# RP2040.net
KiCad netlist of a schematic drawn in Altium Designer
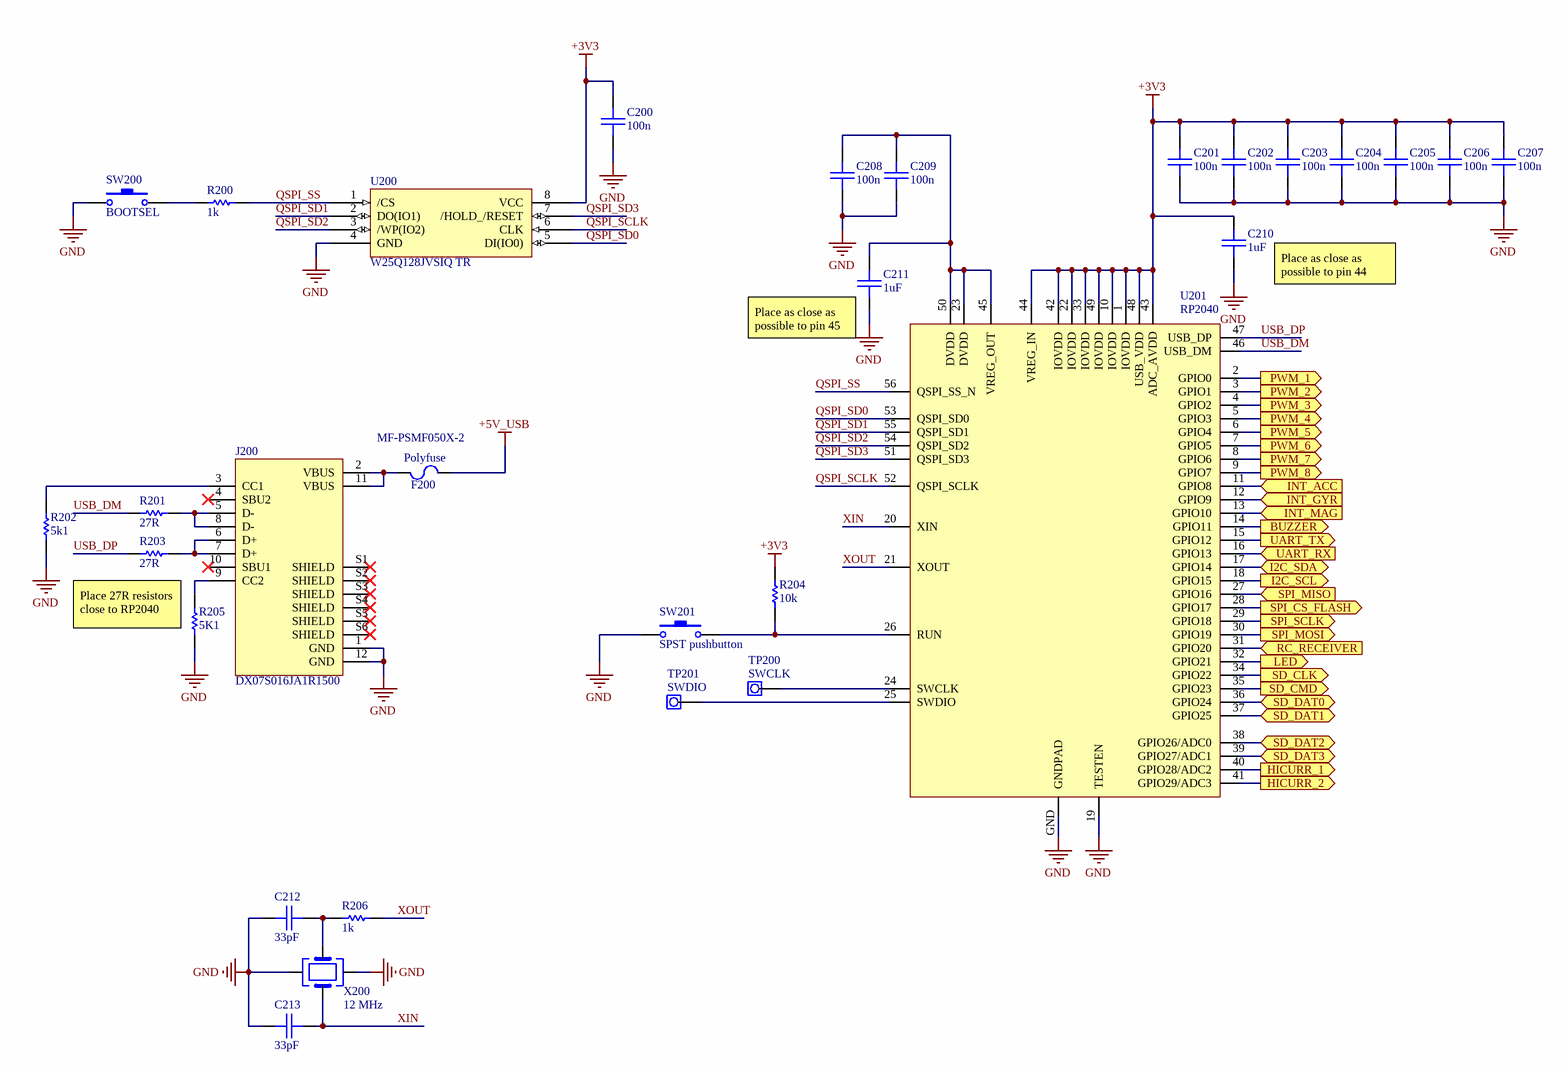
[diagram p0: RP2040.SchDoc]

(export (version "E")
  (design (tool "Eeschema 10.0.6"))
  (components
    (comp (ref "C200")
      (value "100n")
      (footprint "0603_CAP")
      (libsource (lib "Moonlight_Components") (part "Capacitor"))
    )
    (comp (ref "C201")
      (value "100n")
      (footprint "0603_CAP")
      (libsource (lib "Moonlight_Components") (part "Capacitor"))
    )
    (comp (ref "C202")
      (value "100n")
      (footprint "0603_CAP")
      (libsource (lib "Moonlight_Components") (part "Capacitor"))
    )
    (comp (ref "C203")
      (value "100n")
      (footprint "0603_CAP")
      (libsource (lib "Moonlight_Components") (part "Capacitor"))
    )
    (comp (ref "C204")
      (value "100n")
      (footprint "0603_CAP")
      (libsource (lib "Moonlight_Components") (part "Capacitor"))
    )
    (comp (ref "C205")
      (value "100n")
      (footprint "0603_CAP")
      (libsource (lib "Moonlight_Components") (part "Capacitor"))
    )
    (comp (ref "C206")
      (value "100n")
      (footprint "0603_CAP")
      (libsource (lib "Moonlight_Components") (part "Capacitor"))
    )
    (comp (ref "C207")
      (value "100n")
      (footprint "0603_CAP")
      (libsource (lib "Moonlight_Components") (part "Capacitor"))
    )
    (comp (ref "C208")
      (value "100n")
      (footprint "0603_CAP")
      (libsource (lib "Moonlight_Components") (part "Capacitor"))
    )
    (comp (ref "C209")
      (value "100n")
      (footprint "0603_CAP")
      (libsource (lib "Moonlight_Components") (part "Capacitor"))
    )
    (comp (ref "C210")
      (value "1uF")
      (footprint "0603_CAP")
      (libsource (lib "Moonlight_Components") (part "Capacitor"))
    )
    (comp (ref "C211")
      (value "1uF")
      (footprint "0603_CAP")
      (libsource (lib "Moonlight_Components") (part "Capacitor"))
    )
    (comp (ref "C212")
      (value "33pF")
      (footprint "0603_CAP")
      (libsource (lib "Moonlight_Components") (part "Capacitor"))
    )
    (comp (ref "C213")
      (value "33pF")
      (footprint "0603_CAP")
      (libsource (lib "Moonlight_Components") (part "Capacitor"))
    )
    (comp (ref "F200")
      (value "Polyfuse")
      (footprint "0805")
      (libsource (lib "Moonlight_Components") (part "Fuse"))
    )
    (comp (ref "J200")
      (value "DX07S016JA1R1500")
      (footprint "JAE_DX07S016JA1R1500")
      (description "USB 2.0 Type C Receptacle Dip Type, PCB Top Mount (Digikey part no. 670-DX07S016JA1R1500CT-ND)")
      (fields (field (name "MF") "JAE Electronics"))
      (libsource (lib "Moonlight_Components") (part "DX07S016JA1R1500"))
    )
    (comp (ref "R200")
      (value "1k")
      (footprint "0603_RES")
      (libsource (lib "Moonlight_Components") (part "Resistor"))
    )
    (comp (ref "R201")
      (value "27R")
      (footprint "0603_RES")
      (libsource (lib "Moonlight_Components") (part "Resistor"))
    )
    (comp (ref "R202")
      (value "5k1")
      (footprint "0603_RES")
      (libsource (lib "Moonlight_Components") (part "Resistor"))
    )
    (comp (ref "R203")
      (value "27R")
      (footprint "0603_RES")
      (libsource (lib "Moonlight_Components") (part "Resistor"))
    )
    (comp (ref "R204")
      (value "10k")
      (footprint "0805_RES")
      (libsource (lib "Moonlight_Components") (part "Resistor"))
    )
    (comp (ref "R205")
      (value "5K1")
      (footprint "0603_RES")
      (libsource (lib "Moonlight_Components") (part "Resistor"))
    )
    (comp (ref "R206")
      (value "1k")
      (footprint "0603_RES")
      (libsource (lib "Moonlight_Components") (part "Resistor"))
    )
    (comp (ref "SW200")
      (value "BOOTSEL")
      (footprint "TL1015")
      (description "DigiKey part no. EG4344CT-ND")
      (libsource (lib "Moonlight_Components") (part "PushButton"))
    )
    (comp (ref "SW201")
      (value "SPST pushbutton")
      (footprint "TL1015")
      (description "DigiKey part no. EG4344CT-ND")
      (libsource (lib "Moonlight_Components") (part "PushButton"))
    )
    (comp (ref "TP200")
      (value "SWCLK")
      (footprint "Testpoint")
      (libsource (lib "Moonlight_Components") (part "Testpoint"))
    )
    (comp (ref "TP201")
      (value "SWDIO")
      (footprint "Testpoint")
      (libsource (lib "Moonlight_Components") (part "Testpoint"))
    )
    (comp (ref "U200")
      (value "W25Q128JVSIQ TR")
      (footprint "SOIC_208MIL_WIN")
      (description "No Description Available")
      (fields (field (name "COPYRIGHT") "Copyright (C) 2018 Accelerated Designs. All rights reserved"))
      (libsource (lib "Moonlight_Components") (part "W25Q128JVSIQ TR"))
    )
    (comp (ref "U201")
      (value "RP2040")
      (footprint "RP2040")
      (libsource (lib "Moonlight_Components") (part "RP2040"))
    )
    (comp (ref "X200")
      (value "12 MHz")
      (footprint "XOSC_3.2mmx2.5mm")
      (description "12 MHz crystal oscillator\r\nECS-120-20-33-CKM-TR\r\nDigiKey part no. XC1810CT-ND")
      (libsource (lib "Moonlight_Components") (part "XTAL_12 MHz"))
    )
  )
  (nets
    (net (code "1") (name "+3V3") (class "Default")
      (node (ref "C200") (pin "1") (pinfunction "1_1") (pintype "passive"))
      (node (ref "C201") (pin "1") (pinfunction "1_1") (pintype "passive"))
      (node (ref "C202") (pin "1") (pinfunction "1_1") (pintype "passive"))
      (node (ref "C203") (pin "1") (pinfunction "1_1") (pintype "passive"))
      (node (ref "C204") (pin "1") (pinfunction "1_1") (pintype "passive"))
      (node (ref "C205") (pin "1") (pinfunction "1_1") (pintype "passive"))
      (node (ref "C206") (pin "1") (pinfunction "1_1") (pintype "passive"))
      (node (ref "C207") (pin "1") (pinfunction "1_1") (pintype "passive"))
      (node (ref "C210") (pin "1") (pinfunction "1_1") (pintype "passive"))
      (node (ref "R204") (pin "1") (pinfunction "1_1") (pintype "passive"))
      (node (ref "U200") (pin "8") (pinfunction "VCC_8") (pintype "power_in"))
      (node (ref "U201") (pin "1") (pinfunction "IOVDD_1") (pintype "passive"))
      (node (ref "U201") (pin "10") (pinfunction "IOVDD_10") (pintype "passive"))
      (node (ref "U201") (pin "22") (pinfunction "IOVDD_22") (pintype "passive"))
      (node (ref "U201") (pin "33") (pinfunction "IOVDD_33") (pintype "passive"))
      (node (ref "U201") (pin "42") (pinfunction "IOVDD_42") (pintype "passive"))
      (node (ref "U201") (pin "43") (pinfunction "ADC_AVDD_43") (pintype "passive"))
      (node (ref "U201") (pin "44") (pinfunction "VREG_IN_44") (pintype "passive"))
      (node (ref "U201") (pin "48") (pinfunction "USB_VDD_48") (pintype "passive"))
      (node (ref "U201") (pin "49") (pinfunction "IOVDD_49") (pintype "passive"))
    )
    (net (code "2") (name "+5V_USB") (class "Default")
      (node (ref "F200") (pin "2") (pinfunction "2_2") (pintype "passive"))
    )
    (net (code "3") (name "/BUZZER") (class "Default")
      (node (ref "U201") (pin "14") (pinfunction "GPIO11_14") (pintype "passive"))
    )
    (net (code "4") (name "/HICURR_1") (class "Default")
      (node (ref "U201") (pin "40") (pinfunction "GPIO28/ADC2_40") (pintype "passive"))
    )
    (net (code "5") (name "/HICURR_2") (class "Default")
      (node (ref "U201") (pin "41") (pinfunction "GPIO29/ADC3_41") (pintype "passive"))
    )
    (net (code "6") (name "/I2C_SCL") (class "Default")
      (node (ref "U201") (pin "18") (pinfunction "GPIO15_18") (pintype "passive"))
    )
    (net (code "7") (name "/I2C_SDA") (class "Default")
      (node (ref "U201") (pin "17") (pinfunction "GPIO14_17") (pintype "passive"))
    )
    (net (code "8") (name "/INT_ACC") (class "Default")
      (node (ref "U201") (pin "11") (pinfunction "GPIO8_11") (pintype "passive"))
    )
    (net (code "9") (name "/INT_GYR") (class "Default")
      (node (ref "U201") (pin "12") (pinfunction "GPIO9_12") (pintype "passive"))
    )
    (net (code "10") (name "/INT_MAG") (class "Default")
      (node (ref "U201") (pin "13") (pinfunction "GPIO10_13") (pintype "passive"))
    )
    (net (code "11") (name "/LED") (class "Default")
      (node (ref "U201") (pin "32") (pinfunction "GPIO21_32") (pintype "passive"))
    )
    (net (code "12") (name "/PWM_1") (class "Default")
      (node (ref "U201") (pin "2") (pinfunction "GPIO0_2") (pintype "passive"))
    )
    (net (code "13") (name "/PWM_2") (class "Default")
      (node (ref "U201") (pin "3") (pinfunction "GPIO1_3") (pintype "passive"))
    )
    (net (code "14") (name "/PWM_3") (class "Default")
      (node (ref "U201") (pin "4") (pinfunction "GPIO2_4") (pintype "passive"))
    )
    (net (code "15") (name "/PWM_4") (class "Default")
      (node (ref "U201") (pin "5") (pinfunction "GPIO3_5") (pintype "passive"))
    )
    (net (code "16") (name "/PWM_5") (class "Default")
      (node (ref "U201") (pin "6") (pinfunction "GPIO4_6") (pintype "passive"))
    )
    (net (code "17") (name "/PWM_6") (class "Default")
      (node (ref "U201") (pin "7") (pinfunction "GPIO5_7") (pintype "passive"))
    )
    (net (code "18") (name "/PWM_7") (class "Default")
      (node (ref "U201") (pin "8") (pinfunction "GPIO6_8") (pintype "passive"))
    )
    (net (code "19") (name "/PWM_8") (class "Default")
      (node (ref "U201") (pin "9") (pinfunction "GPIO7_9") (pintype "passive"))
    )
    (net (code "20") (name "/QSPI_SCLK") (class "Default")
      (node (ref "U200") (pin "6") (pinfunction "CLK_6") (pintype "input"))
      (node (ref "U201") (pin "52") (pinfunction "QSPI_SCLK_52") (pintype "passive"))
    )
    (net (code "21") (name "/QSPI_SD0") (class "Default")
      (node (ref "U200") (pin "5") (pinfunction "DI(IO0)_5") (pintype "bidirectional"))
      (node (ref "U201") (pin "53") (pinfunction "QSPI_SD0_53") (pintype "passive"))
    )
    (net (code "22") (name "/QSPI_SD1") (class "Default")
      (node (ref "U200") (pin "2") (pinfunction "DO(IO1)_2") (pintype "bidirectional"))
      (node (ref "U201") (pin "55") (pinfunction "QSPI_SD1_55") (pintype "passive"))
    )
    (net (code "23") (name "/QSPI_SD2") (class "Default")
      (node (ref "U200") (pin "3") (pinfunction "/WP(IO2)_3") (pintype "bidirectional"))
      (node (ref "U201") (pin "54") (pinfunction "QSPI_SD2_54") (pintype "passive"))
    )
    (net (code "24") (name "/QSPI_SD3") (class "Default")
      (node (ref "U200") (pin "7") (pinfunction "/HOLD_/RESET_7") (pintype "bidirectional"))
      (node (ref "U201") (pin "51") (pinfunction "QSPI_SD3_51") (pintype "passive"))
    )
    (net (code "25") (name "/QSPI_SS") (class "Default")
      (node (ref "R200") (pin "2") (pinfunction "2_2") (pintype "passive"))
      (node (ref "U200") (pin "1") (pinfunction "/CS_1") (pintype "input"))
      (node (ref "U201") (pin "56") (pinfunction "QSPI_SS_N_56") (pintype "passive"))
    )
    (net (code "26") (name "/RC_RECEIVER") (class "Default")
      (node (ref "U201") (pin "31") (pinfunction "GPIO20_31") (pintype "passive"))
    )
    (net (code "27") (name "/SD_CLK") (class "Default")
      (node (ref "U201") (pin "34") (pinfunction "GPIO22_34") (pintype "passive"))
    )
    (net (code "28") (name "/SD_CMD") (class "Default")
      (node (ref "U201") (pin "35") (pinfunction "GPIO23_35") (pintype "passive"))
    )
    (net (code "29") (name "/SD_DAT0") (class "Default")
      (node (ref "U201") (pin "36") (pinfunction "GPIO24_36") (pintype "passive"))
    )
    (net (code "30") (name "/SD_DAT1") (class "Default")
      (node (ref "U201") (pin "37") (pinfunction "GPIO25_37") (pintype "passive"))
    )
    (net (code "31") (name "/SD_DAT2") (class "Default")
      (node (ref "U201") (pin "38") (pinfunction "GPIO26/ADC0_38") (pintype "passive"))
    )
    (net (code "32") (name "/SD_DAT3") (class "Default")
      (node (ref "U201") (pin "39") (pinfunction "GPIO27/ADC1_39") (pintype "passive"))
    )
    (net (code "33") (name "/SPI_CS_FLASH") (class "Default")
      (node (ref "U201") (pin "28") (pinfunction "GPIO17_28") (pintype "passive"))
    )
    (net (code "34") (name "/SPI_MISO") (class "Default")
      (node (ref "U201") (pin "27") (pinfunction "GPIO16_27") (pintype "passive"))
    )
    (net (code "35") (name "/SPI_MOSI") (class "Default")
      (node (ref "U201") (pin "30") (pinfunction "GPIO19_30") (pintype "passive"))
    )
    (net (code "36") (name "/SPI_SCLK") (class "Default")
      (node (ref "U201") (pin "29") (pinfunction "GPIO18_29") (pintype "passive"))
    )
    (net (code "37") (name "/UART_RX") (class "Default")
      (node (ref "U201") (pin "16") (pinfunction "GPIO13_16") (pintype "passive"))
    )
    (net (code "38") (name "/UART_TX") (class "Default")
      (node (ref "U201") (pin "15") (pinfunction "GPIO12_15") (pintype "passive"))
    )
    (net (code "39") (name "/USB_DM") (class "Default")
      (node (ref "R201") (pin "1") (pinfunction "1_1") (pintype "passive"))
      (node (ref "U201") (pin "46") (pinfunction "USB_DM_46") (pintype "passive"))
    )
    (net (code "40") (name "/USB_DP") (class "Default")
      (node (ref "R203") (pin "1") (pinfunction "1_1") (pintype "passive"))
      (node (ref "U201") (pin "47") (pinfunction "USB_DP_47") (pintype "passive"))
    )
    (net (code "41") (name "/XIN") (class "Default")
      (node (ref "C213") (pin "1") (pinfunction "1_1") (pintype "passive"))
      (node (ref "U201") (pin "20") (pinfunction "XIN_20") (pintype "passive"))
      (node (ref "X200") (pin "1") (pinfunction "1_1") (pintype "passive"))
    )
    (net (code "42") (name "/XOUT") (class "Default")
      (node (ref "R206") (pin "1") (pinfunction "1_1") (pintype "passive"))
      (node (ref "U201") (pin "21") (pinfunction "XOUT_21") (pintype "passive"))
    )
    (net (code "43") (name "GND") (class "Default")
      (node (ref "C200") (pin "2") (pinfunction "2_2") (pintype "passive"))
      (node (ref "C201") (pin "2") (pinfunction "2_2") (pintype "passive"))
      (node (ref "C202") (pin "2") (pinfunction "2_2") (pintype "passive"))
      (node (ref "C203") (pin "2") (pinfunction "2_2") (pintype "passive"))
      (node (ref "C204") (pin "2") (pinfunction "2_2") (pintype "passive"))
      (node (ref "C205") (pin "2") (pinfunction "2_2") (pintype "passive"))
      (node (ref "C206") (pin "2") (pinfunction "2_2") (pintype "passive"))
      (node (ref "C207") (pin "2") (pinfunction "2_2") (pintype "passive"))
      (node (ref "C208") (pin "2") (pinfunction "2_2") (pintype "passive"))
      (node (ref "C209") (pin "2") (pinfunction "2_2") (pintype "passive"))
      (node (ref "C210") (pin "2") (pinfunction "2_2") (pintype "passive"))
      (node (ref "C211") (pin "2") (pinfunction "2_2") (pintype "passive"))
      (node (ref "C212") (pin "2") (pinfunction "2_2") (pintype "passive"))
      (node (ref "C213") (pin "2") (pinfunction "2_2") (pintype "passive"))
      (node (ref "J200") (pin "1") (pinfunction "GND_1") (pintype "power_in"))
      (node (ref "J200") (pin "12") (pinfunction "GND_12") (pintype "power_in"))
      (node (ref "R202") (pin "2") (pinfunction "2_2") (pintype "passive"))
      (node (ref "R205") (pin "2") (pinfunction "2_2") (pintype "passive"))
      (node (ref "SW200") (pin "1") (pinfunction "1_1") (pintype "passive"))
      (node (ref "SW201") (pin "1") (pinfunction "1_1") (pintype "passive"))
      (node (ref "U200") (pin "4") (pinfunction "GND_4") (pintype "passive"))
      (node (ref "U201") (pin "19") (pinfunction "TESTEN_19") (pintype "passive"))
      (node (ref "U201") (pin "GND") (pinfunction "GNDPAD_GND") (pintype "passive"))
      (node (ref "X200") (pin "2") (pinfunction "2_2") (pintype "passive"))
      (node (ref "X200") (pin "4") (pinfunction "4_4") (pintype "passive"))
    )
    (net (code "44") (name "Net-(C212-Pad1)") (class "Default")
      (node (ref "C212") (pin "1") (pinfunction "1_1") (pintype "passive"))
      (node (ref "R206") (pin "2") (pinfunction "2_2") (pintype "passive"))
      (node (ref "X200") (pin "3") (pinfunction "3_3") (pintype "passive"))
    )
    (net (code "45") (name "Net-(F200-Pad1)") (class "Default")
      (node (ref "F200") (pin "1") (pinfunction "1_1") (pintype "passive"))
      (node (ref "J200") (pin "11") (pinfunction "VBUS_11") (pintype "power_in"))
      (node (ref "J200") (pin "2") (pinfunction "VBUS_2") (pintype "power_in"))
    )
    (net (code "46") (name "Net-(J200-CC1)") (class "Default")
      (node (ref "J200") (pin "3") (pinfunction "CC1_3") (pintype "passive"))
      (node (ref "R202") (pin "1") (pinfunction "1_1") (pintype "passive"))
    )
    (net (code "47") (name "Net-(J200-CC2)") (class "Default")
      (node (ref "J200") (pin "9") (pinfunction "CC2_9") (pintype "passive"))
      (node (ref "R205") (pin "1") (pinfunction "1_1") (pintype "passive"))
    )
    (net (code "48") (name "Net-(J200-D+-Pad6)") (class "Default")
      (node (ref "J200") (pin "6") (pinfunction "D+_6") (pintype "passive"))
      (node (ref "J200") (pin "7") (pinfunction "D+_7") (pintype "passive"))
      (node (ref "R203") (pin "2") (pinfunction "2_2") (pintype "passive"))
    )
    (net (code "49") (name "Net-(J200-D--Pad5)") (class "Default")
      (node (ref "J200") (pin "5") (pinfunction "D-_5") (pintype "passive"))
      (node (ref "J200") (pin "8") (pinfunction "D-_8") (pintype "passive"))
      (node (ref "R201") (pin "2") (pinfunction "2_2") (pintype "passive"))
    )
    (net (code "50") (name "Net-(R200-Pad1)") (class "Default")
      (node (ref "R200") (pin "1") (pinfunction "1_1") (pintype "passive"))
      (node (ref "SW200") (pin "2") (pinfunction "2_2") (pintype "passive"))
    )
    (net (code "51") (name "Net-(U201-RUN)") (class "Default")
      (node (ref "R204") (pin "2") (pinfunction "2_2") (pintype "passive"))
      (node (ref "SW201") (pin "2") (pinfunction "2_2") (pintype "passive"))
      (node (ref "U201") (pin "26") (pinfunction "RUN_26") (pintype "passive"))
    )
    (net (code "52") (name "Net-(U201-SWCLK)") (class "Default")
      (node (ref "TP200") (pin "1") (pinfunction "1_1") (pintype "passive"))
      (node (ref "U201") (pin "24") (pinfunction "SWCLK_24") (pintype "passive"))
    )
    (net (code "53") (name "Net-(U201-SWDIO)") (class "Default")
      (node (ref "TP201") (pin "1") (pinfunction "1_1") (pintype "passive"))
      (node (ref "U201") (pin "25") (pinfunction "SWDIO_25") (pintype "passive"))
    )
    (net (code "54") (name "Net-(U201-VREG_OUT)") (class "Default")
      (node (ref "C208") (pin "1") (pinfunction "1_1") (pintype "passive"))
      (node (ref "C209") (pin "1") (pinfunction "1_1") (pintype "passive"))
      (node (ref "C211") (pin "1") (pinfunction "1_1") (pintype "passive"))
      (node (ref "U201") (pin "23") (pinfunction "DVDD_23") (pintype "passive"))
      (node (ref "U201") (pin "45") (pinfunction "VREG_OUT_45") (pintype "passive"))
      (node (ref "U201") (pin "50") (pinfunction "DVDD_50") (pintype "passive"))
    )
    (net (code "55") (name "unconnected-(J200-SBU1-Pad10)") (class "Default")
      (node (ref "J200") (pin "10") (pinfunction "SBU1_10") (pintype "passive+no_connect"))
    )
    (net (code "56") (name "unconnected-(J200-SBU2-Pad4)") (class "Default")
      (node (ref "J200") (pin "4") (pinfunction "SBU2_4") (pintype "passive+no_connect"))
    )
    (net (code "57") (name "unconnected-(J200-SHIELD-PadS1)") (class "Default")
      (node (ref "J200") (pin "S1") (pinfunction "SHIELD_S1") (pintype "passive+no_connect"))
    )
    (net (code "58") (name "unconnected-(J200-SHIELD-PadS2)") (class "Default")
      (node (ref "J200") (pin "S2") (pinfunction "SHIELD_S2") (pintype "passive+no_connect"))
    )
    (net (code "59") (name "unconnected-(J200-SHIELD-PadS3)") (class "Default")
      (node (ref "J200") (pin "S3") (pinfunction "SHIELD_S3") (pintype "passive+no_connect"))
    )
    (net (code "60") (name "unconnected-(J200-SHIELD-PadS4)") (class "Default")
      (node (ref "J200") (pin "S4") (pinfunction "SHIELD_S4") (pintype "passive+no_connect"))
    )
    (net (code "61") (name "unconnected-(J200-SHIELD-PadS5)") (class "Default")
      (node (ref "J200") (pin "S5") (pinfunction "SHIELD_S5") (pintype "passive+no_connect"))
    )
    (net (code "62") (name "unconnected-(J200-SHIELD-PadS6)") (class "Default")
      (node (ref "J200") (pin "S6") (pinfunction "SHIELD_S6") (pintype "passive+no_connect"))
    )
  )
)
